# Matrix.net
KiCad netlist of a schematic drawn in Altium Designer
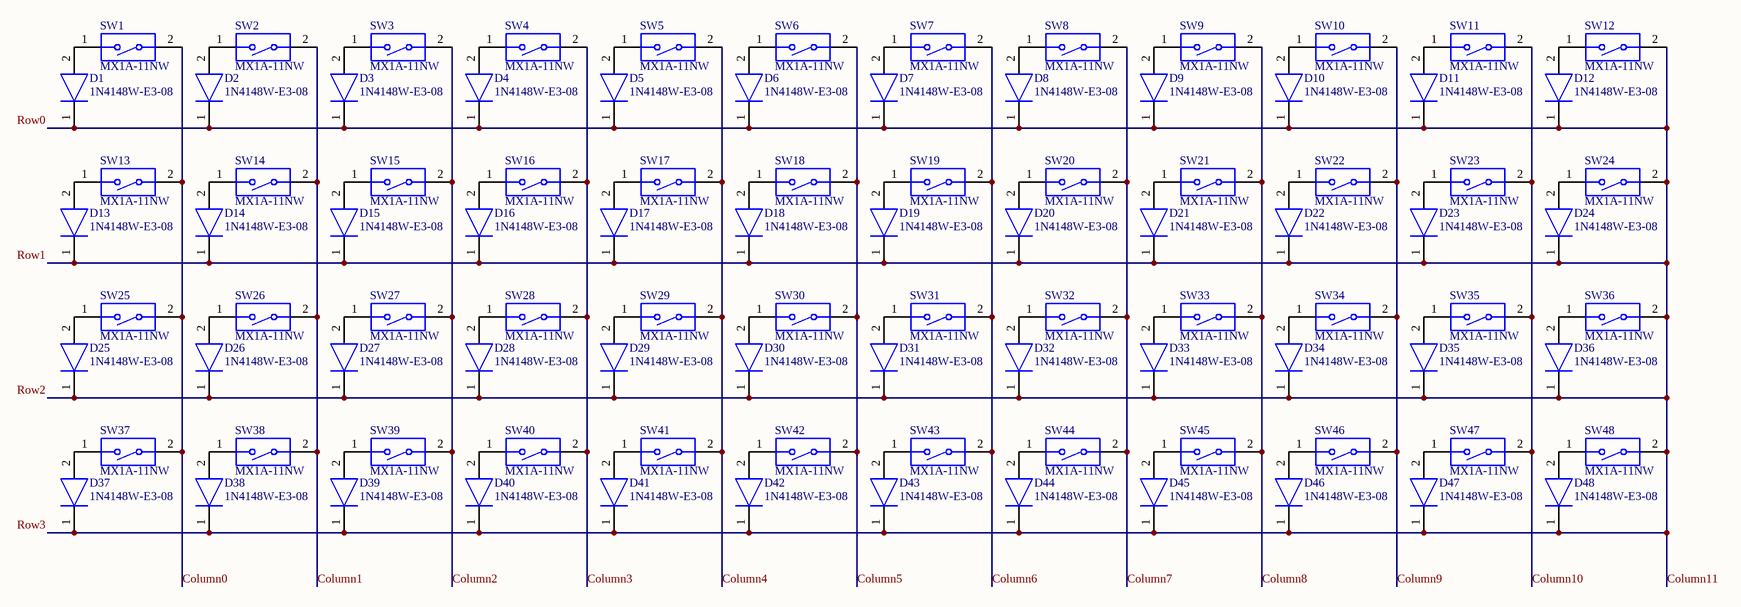
[diagram p0: Matrix.SchDoc]

(export (version "E")
  (design (tool "Eeschema 10.0.6"))
  (components
    (comp (ref "D1")
      (value "1N4148W-E3-08")
      (footprint "SamacSys:SOD3716X135N")
      (description "Diode")
      (fields (field (name "MOUSER PART NUMBER") "78-1N4148W-E3-08"))
      (libsource (lib "*") (part "1N4148W-E3-08"))
    )
    (comp (ref "D2")
      (value "1N4148W-E3-08")
      (footprint "SamacSys:SOD3716X135N")
      (description "Diode")
      (fields (field (name "MOUSER PART NUMBER") "78-1N4148W-E3-08"))
      (libsource (lib "*") (part "1N4148W-E3-08"))
    )
    (comp (ref "D3")
      (value "1N4148W-E3-08")
      (footprint "SamacSys:SOD3716X135N")
      (description "Diode")
      (fields (field (name "MOUSER PART NUMBER") "78-1N4148W-E3-08"))
      (libsource (lib "*") (part "1N4148W-E3-08"))
    )
    (comp (ref "D4")
      (value "1N4148W-E3-08")
      (footprint "SamacSys:SOD3716X135N")
      (description "Diode")
      (fields (field (name "MOUSER PART NUMBER") "78-1N4148W-E3-08"))
      (libsource (lib "*") (part "1N4148W-E3-08"))
    )
    (comp (ref "D5")
      (value "1N4148W-E3-08")
      (footprint "SamacSys:SOD3716X135N")
      (description "Diode")
      (fields (field (name "MOUSER PART NUMBER") "78-1N4148W-E3-08"))
      (libsource (lib "*") (part "1N4148W-E3-08"))
    )
    (comp (ref "D6")
      (value "1N4148W-E3-08")
      (footprint "SamacSys:SOD3716X135N")
      (description "Diode")
      (fields (field (name "MOUSER PART NUMBER") "78-1N4148W-E3-08"))
      (libsource (lib "*") (part "1N4148W-E3-08"))
    )
    (comp (ref "D7")
      (value "1N4148W-E3-08")
      (footprint "SamacSys:SOD3716X135N")
      (description "Diode")
      (fields (field (name "MOUSER PART NUMBER") "78-1N4148W-E3-08"))
      (libsource (lib "*") (part "1N4148W-E3-08"))
    )
    (comp (ref "D8")
      (value "1N4148W-E3-08")
      (footprint "SamacSys:SOD3716X135N")
      (description "Diode")
      (fields (field (name "MOUSER PART NUMBER") "78-1N4148W-E3-08"))
      (libsource (lib "*") (part "1N4148W-E3-08"))
    )
    (comp (ref "D9")
      (value "1N4148W-E3-08")
      (footprint "SamacSys:SOD3716X135N")
      (description "Diode")
      (fields (field (name "MOUSER PART NUMBER") "78-1N4148W-E3-08"))
      (libsource (lib "*") (part "1N4148W-E3-08"))
    )
    (comp (ref "D10")
      (value "1N4148W-E3-08")
      (footprint "SamacSys:SOD3716X135N")
      (description "Diode")
      (fields (field (name "MOUSER PART NUMBER") "78-1N4148W-E3-08"))
      (libsource (lib "*") (part "1N4148W-E3-08"))
    )
    (comp (ref "D11")
      (value "1N4148W-E3-08")
      (footprint "SamacSys:SOD3716X135N")
      (description "Diode")
      (fields (field (name "MOUSER PART NUMBER") "78-1N4148W-E3-08"))
      (libsource (lib "*") (part "1N4148W-E3-08"))
    )
    (comp (ref "D12")
      (value "1N4148W-E3-08")
      (footprint "SamacSys:SOD3716X135N")
      (description "Diode")
      (fields (field (name "MOUSER PART NUMBER") "78-1N4148W-E3-08"))
      (libsource (lib "*") (part "1N4148W-E3-08"))
    )
    (comp (ref "D13")
      (value "1N4148W-E3-08")
      (footprint "SamacSys:SOD3716X135N")
      (description "Diode")
      (fields (field (name "MOUSER PART NUMBER") "78-1N4148W-E3-08"))
      (libsource (lib "*") (part "1N4148W-E3-08"))
    )
    (comp (ref "D14")
      (value "1N4148W-E3-08")
      (footprint "SamacSys:SOD3716X135N")
      (description "Diode")
      (fields (field (name "MOUSER PART NUMBER") "78-1N4148W-E3-08"))
      (libsource (lib "*") (part "1N4148W-E3-08"))
    )
    (comp (ref "D15")
      (value "1N4148W-E3-08")
      (footprint "SamacSys:SOD3716X135N")
      (description "Diode")
      (fields (field (name "MOUSER PART NUMBER") "78-1N4148W-E3-08"))
      (libsource (lib "*") (part "1N4148W-E3-08"))
    )
    (comp (ref "D16")
      (value "1N4148W-E3-08")
      (footprint "SamacSys:SOD3716X135N")
      (description "Diode")
      (fields (field (name "MOUSER PART NUMBER") "78-1N4148W-E3-08"))
      (libsource (lib "*") (part "1N4148W-E3-08"))
    )
    (comp (ref "D17")
      (value "1N4148W-E3-08")
      (footprint "SamacSys:SOD3716X135N")
      (description "Diode")
      (fields (field (name "MOUSER PART NUMBER") "78-1N4148W-E3-08"))
      (libsource (lib "*") (part "1N4148W-E3-08"))
    )
    (comp (ref "D18")
      (value "1N4148W-E3-08")
      (footprint "SamacSys:SOD3716X135N")
      (description "Diode")
      (fields (field (name "MOUSER PART NUMBER") "78-1N4148W-E3-08"))
      (libsource (lib "*") (part "1N4148W-E3-08"))
    )
    (comp (ref "D19")
      (value "1N4148W-E3-08")
      (footprint "SamacSys:SOD3716X135N")
      (description "Diode")
      (fields (field (name "MOUSER PART NUMBER") "78-1N4148W-E3-08"))
      (libsource (lib "*") (part "1N4148W-E3-08"))
    )
    (comp (ref "D20")
      (value "1N4148W-E3-08")
      (footprint "SamacSys:SOD3716X135N")
      (description "Diode")
      (fields (field (name "MOUSER PART NUMBER") "78-1N4148W-E3-08"))
      (libsource (lib "*") (part "1N4148W-E3-08"))
    )
    (comp (ref "D21")
      (value "1N4148W-E3-08")
      (footprint "SamacSys:SOD3716X135N")
      (description "Diode")
      (fields (field (name "MOUSER PART NUMBER") "78-1N4148W-E3-08"))
      (libsource (lib "*") (part "1N4148W-E3-08"))
    )
    (comp (ref "D22")
      (value "1N4148W-E3-08")
      (footprint "SamacSys:SOD3716X135N")
      (description "Diode")
      (fields (field (name "MOUSER PART NUMBER") "78-1N4148W-E3-08"))
      (libsource (lib "*") (part "1N4148W-E3-08"))
    )
    (comp (ref "D23")
      (value "1N4148W-E3-08")
      (footprint "SamacSys:SOD3716X135N")
      (description "Diode")
      (fields (field (name "MOUSER PART NUMBER") "78-1N4148W-E3-08"))
      (libsource (lib "*") (part "1N4148W-E3-08"))
    )
    (comp (ref "D24")
      (value "1N4148W-E3-08")
      (footprint "SamacSys:SOD3716X135N")
      (description "Diode")
      (fields (field (name "MOUSER PART NUMBER") "78-1N4148W-E3-08"))
      (libsource (lib "*") (part "1N4148W-E3-08"))
    )
    (comp (ref "D25")
      (value "1N4148W-E3-08")
      (footprint "SamacSys:SOD3716X135N")
      (description "Diode")
      (fields (field (name "MOUSER PART NUMBER") "78-1N4148W-E3-08"))
      (libsource (lib "*") (part "1N4148W-E3-08"))
    )
    (comp (ref "D26")
      (value "1N4148W-E3-08")
      (footprint "SamacSys:SOD3716X135N")
      (description "Diode")
      (fields (field (name "MOUSER PART NUMBER") "78-1N4148W-E3-08"))
      (libsource (lib "*") (part "1N4148W-E3-08"))
    )
    (comp (ref "D27")
      (value "1N4148W-E3-08")
      (footprint "SamacSys:SOD3716X135N")
      (description "Diode")
      (fields (field (name "MOUSER PART NUMBER") "78-1N4148W-E3-08"))
      (libsource (lib "*") (part "1N4148W-E3-08"))
    )
    (comp (ref "D28")
      (value "1N4148W-E3-08")
      (footprint "SamacSys:SOD3716X135N")
      (description "Diode")
      (fields (field (name "MOUSER PART NUMBER") "78-1N4148W-E3-08"))
      (libsource (lib "*") (part "1N4148W-E3-08"))
    )
    (comp (ref "D29")
      (value "1N4148W-E3-08")
      (footprint "SamacSys:SOD3716X135N")
      (description "Diode")
      (fields (field (name "MOUSER PART NUMBER") "78-1N4148W-E3-08"))
      (libsource (lib "*") (part "1N4148W-E3-08"))
    )
    (comp (ref "D30")
      (value "1N4148W-E3-08")
      (footprint "SamacSys:SOD3716X135N")
      (description "Diode")
      (fields (field (name "MOUSER PART NUMBER") "78-1N4148W-E3-08"))
      (libsource (lib "*") (part "1N4148W-E3-08"))
    )
    (comp (ref "D31")
      (value "1N4148W-E3-08")
      (footprint "SamacSys:SOD3716X135N")
      (description "Diode")
      (fields (field (name "MOUSER PART NUMBER") "78-1N4148W-E3-08"))
      (libsource (lib "*") (part "1N4148W-E3-08"))
    )
    (comp (ref "D32")
      (value "1N4148W-E3-08")
      (footprint "SamacSys:SOD3716X135N")
      (description "Diode")
      (fields (field (name "MOUSER PART NUMBER") "78-1N4148W-E3-08"))
      (libsource (lib "*") (part "1N4148W-E3-08"))
    )
    (comp (ref "D33")
      (value "1N4148W-E3-08")
      (footprint "SamacSys:SOD3716X135N")
      (description "Diode")
      (fields (field (name "MOUSER PART NUMBER") "78-1N4148W-E3-08"))
      (libsource (lib "*") (part "1N4148W-E3-08"))
    )
    (comp (ref "D34")
      (value "1N4148W-E3-08")
      (footprint "SamacSys:SOD3716X135N")
      (description "Diode")
      (fields (field (name "MOUSER PART NUMBER") "78-1N4148W-E3-08"))
      (libsource (lib "*") (part "1N4148W-E3-08"))
    )
    (comp (ref "D35")
      (value "1N4148W-E3-08")
      (footprint "SamacSys:SOD3716X135N")
      (description "Diode")
      (fields (field (name "MOUSER PART NUMBER") "78-1N4148W-E3-08"))
      (libsource (lib "*") (part "1N4148W-E3-08"))
    )
    (comp (ref "D36")
      (value "1N4148W-E3-08")
      (footprint "SamacSys:SOD3716X135N")
      (description "Diode")
      (fields (field (name "MOUSER PART NUMBER") "78-1N4148W-E3-08"))
      (libsource (lib "*") (part "1N4148W-E3-08"))
    )
    (comp (ref "D37")
      (value "1N4148W-E3-08")
      (footprint "SamacSys:SOD3716X135N")
      (description "Diode")
      (fields (field (name "MOUSER PART NUMBER") "78-1N4148W-E3-08"))
      (libsource (lib "*") (part "1N4148W-E3-08"))
    )
    (comp (ref "D38")
      (value "1N4148W-E3-08")
      (footprint "SamacSys:SOD3716X135N")
      (description "Diode")
      (fields (field (name "MOUSER PART NUMBER") "78-1N4148W-E3-08"))
      (libsource (lib "*") (part "1N4148W-E3-08"))
    )
    (comp (ref "D39")
      (value "1N4148W-E3-08")
      (footprint "SamacSys:SOD3716X135N")
      (description "Diode")
      (fields (field (name "MOUSER PART NUMBER") "78-1N4148W-E3-08"))
      (libsource (lib "*") (part "1N4148W-E3-08"))
    )
    (comp (ref "D40")
      (value "1N4148W-E3-08")
      (footprint "SamacSys:SOD3716X135N")
      (description "Diode")
      (fields (field (name "MOUSER PART NUMBER") "78-1N4148W-E3-08"))
      (libsource (lib "*") (part "1N4148W-E3-08"))
    )
    (comp (ref "D41")
      (value "1N4148W-E3-08")
      (footprint "SamacSys:SOD3716X135N")
      (description "Diode")
      (fields (field (name "MOUSER PART NUMBER") "78-1N4148W-E3-08"))
      (libsource (lib "*") (part "1N4148W-E3-08"))
    )
    (comp (ref "D42")
      (value "1N4148W-E3-08")
      (footprint "SamacSys:SOD3716X135N")
      (description "Diode")
      (fields (field (name "MOUSER PART NUMBER") "78-1N4148W-E3-08"))
      (libsource (lib "*") (part "1N4148W-E3-08"))
    )
    (comp (ref "D43")
      (value "1N4148W-E3-08")
      (footprint "SamacSys:SOD3716X135N")
      (description "Diode")
      (fields (field (name "MOUSER PART NUMBER") "78-1N4148W-E3-08"))
      (libsource (lib "*") (part "1N4148W-E3-08"))
    )
    (comp (ref "D44")
      (value "1N4148W-E3-08")
      (footprint "SamacSys:SOD3716X135N")
      (description "Diode")
      (fields (field (name "MOUSER PART NUMBER") "78-1N4148W-E3-08"))
      (libsource (lib "*") (part "1N4148W-E3-08"))
    )
    (comp (ref "D45")
      (value "1N4148W-E3-08")
      (footprint "SamacSys:SOD3716X135N")
      (description "Diode")
      (fields (field (name "MOUSER PART NUMBER") "78-1N4148W-E3-08"))
      (libsource (lib "*") (part "1N4148W-E3-08"))
    )
    (comp (ref "D46")
      (value "1N4148W-E3-08")
      (footprint "SamacSys:SOD3716X135N")
      (description "Diode")
      (fields (field (name "MOUSER PART NUMBER") "78-1N4148W-E3-08"))
      (libsource (lib "*") (part "1N4148W-E3-08"))
    )
    (comp (ref "D47")
      (value "1N4148W-E3-08")
      (footprint "SamacSys:SOD3716X135N")
      (description "Diode")
      (fields (field (name "MOUSER PART NUMBER") "78-1N4148W-E3-08"))
      (libsource (lib "*") (part "1N4148W-E3-08"))
    )
    (comp (ref "D48")
      (value "1N4148W-E3-08")
      (footprint "SamacSys:SOD3716X135N")
      (description "Diode")
      (fields (field (name "MOUSER PART NUMBER") "78-1N4148W-E3-08"))
      (libsource (lib "*") (part "1N4148W-E3-08"))
    )
    (comp (ref "SW1")
      (value "MX1A-11NW")
      (footprint "CHRY-MX1A-11NW_V")
      (description "Keylock Switch, 12 V, -10 to 70 degC, 2-Pin THD, RoHS, Bulk")
      (fields (field (name "MANUFACTURER") "Cherry") (field (name "PART NO") "MX1A11NW"))
      (libsource (lib "mx1a-11nw") (part "CMP-2000-06786-1"))
    )
    (comp (ref "SW2")
      (value "MX1A-11NW")
      (footprint "CHRY-MX1A-11NW_V")
      (description "Keylock Switch, 12 V, -10 to 70 degC, 2-Pin THD, RoHS, Bulk")
      (fields (field (name "MANUFACTURER") "Cherry") (field (name "PART NO") "MX1A11NW"))
      (libsource (lib "mx1a-11nw") (part "CMP-2000-06786-1"))
    )
    (comp (ref "SW3")
      (value "MX1A-11NW")
      (footprint "CHRY-MX1A-11NW_V")
      (description "Keylock Switch, 12 V, -10 to 70 degC, 2-Pin THD, RoHS, Bulk")
      (fields (field (name "MANUFACTURER") "Cherry") (field (name "PART NO") "MX1A11NW"))
      (libsource (lib "mx1a-11nw") (part "CMP-2000-06786-1"))
    )
    (comp (ref "SW4")
      (value "MX1A-11NW")
      (footprint "CHRY-MX1A-11NW_V")
      (description "Keylock Switch, 12 V, -10 to 70 degC, 2-Pin THD, RoHS, Bulk")
      (fields (field (name "MANUFACTURER") "Cherry") (field (name "PART NO") "MX1A11NW"))
      (libsource (lib "mx1a-11nw") (part "CMP-2000-06786-1"))
    )
    (comp (ref "SW5")
      (value "MX1A-11NW")
      (footprint "CHRY-MX1A-11NW_V")
      (description "Keylock Switch, 12 V, -10 to 70 degC, 2-Pin THD, RoHS, Bulk")
      (fields (field (name "MANUFACTURER") "Cherry") (field (name "PART NO") "MX1A11NW"))
      (libsource (lib "mx1a-11nw") (part "CMP-2000-06786-1"))
    )
    (comp (ref "SW6")
      (value "MX1A-11NW")
      (footprint "CHRY-MX1A-11NW_V")
      (description "Keylock Switch, 12 V, -10 to 70 degC, 2-Pin THD, RoHS, Bulk")
      (fields (field (name "MANUFACTURER") "Cherry") (field (name "PART NO") "MX1A11NW"))
      (libsource (lib "mx1a-11nw") (part "CMP-2000-06786-1"))
    )
    (comp (ref "SW7")
      (value "MX1A-11NW")
      (footprint "CHRY-MX1A-11NW_V")
      (description "Keylock Switch, 12 V, -10 to 70 degC, 2-Pin THD, RoHS, Bulk")
      (fields (field (name "MANUFACTURER") "Cherry") (field (name "PART NO") "MX1A11NW"))
      (libsource (lib "mx1a-11nw") (part "CMP-2000-06786-1"))
    )
    (comp (ref "SW8")
      (value "MX1A-11NW")
      (footprint "CHRY-MX1A-11NW_V")
      (description "Keylock Switch, 12 V, -10 to 70 degC, 2-Pin THD, RoHS, Bulk")
      (fields (field (name "MANUFACTURER") "Cherry") (field (name "PART NO") "MX1A11NW"))
      (libsource (lib "mx1a-11nw") (part "CMP-2000-06786-1"))
    )
    (comp (ref "SW9")
      (value "MX1A-11NW")
      (footprint "CHRY-MX1A-11NW_V")
      (description "Keylock Switch, 12 V, -10 to 70 degC, 2-Pin THD, RoHS, Bulk")
      (fields (field (name "MANUFACTURER") "Cherry") (field (name "PART NO") "MX1A11NW"))
      (libsource (lib "mx1a-11nw") (part "CMP-2000-06786-1"))
    )
    (comp (ref "SW10")
      (value "MX1A-11NW")
      (footprint "CHRY-MX1A-11NW_V")
      (description "Keylock Switch, 12 V, -10 to 70 degC, 2-Pin THD, RoHS, Bulk")
      (fields (field (name "MANUFACTURER") "Cherry") (field (name "PART NO") "MX1A11NW"))
      (libsource (lib "mx1a-11nw") (part "CMP-2000-06786-1"))
    )
    (comp (ref "SW11")
      (value "MX1A-11NW")
      (footprint "CHRY-MX1A-11NW_V")
      (description "Keylock Switch, 12 V, -10 to 70 degC, 2-Pin THD, RoHS, Bulk")
      (fields (field (name "MANUFACTURER") "Cherry") (field (name "PART NO") "MX1A11NW"))
      (libsource (lib "mx1a-11nw") (part "CMP-2000-06786-1"))
    )
    (comp (ref "SW12")
      (value "MX1A-11NW")
      (footprint "CHRY-MX1A-11NW_V")
      (description "Keylock Switch, 12 V, -10 to 70 degC, 2-Pin THD, RoHS, Bulk")
      (fields (field (name "MANUFACTURER") "Cherry") (field (name "PART NO") "MX1A11NW"))
      (libsource (lib "mx1a-11nw") (part "CMP-2000-06786-1"))
    )
    (comp (ref "SW13")
      (value "MX1A-11NW")
      (footprint "CHRY-MX1A-11NW_V")
      (description "Keylock Switch, 12 V, -10 to 70 degC, 2-Pin THD, RoHS, Bulk")
      (fields (field (name "MANUFACTURER") "Cherry") (field (name "PART NO") "MX1A11NW"))
      (libsource (lib "mx1a-11nw") (part "CMP-2000-06786-1"))
    )
    (comp (ref "SW14")
      (value "MX1A-11NW")
      (footprint "CHRY-MX1A-11NW_V")
      (description "Keylock Switch, 12 V, -10 to 70 degC, 2-Pin THD, RoHS, Bulk")
      (fields (field (name "MANUFACTURER") "Cherry") (field (name "PART NO") "MX1A11NW"))
      (libsource (lib "mx1a-11nw") (part "CMP-2000-06786-1"))
    )
    (comp (ref "SW15")
      (value "MX1A-11NW")
      (footprint "CHRY-MX1A-11NW_V")
      (description "Keylock Switch, 12 V, -10 to 70 degC, 2-Pin THD, RoHS, Bulk")
      (fields (field (name "MANUFACTURER") "Cherry") (field (name "PART NO") "MX1A11NW"))
      (libsource (lib "mx1a-11nw") (part "CMP-2000-06786-1"))
    )
    (comp (ref "SW16")
      (value "MX1A-11NW")
      (footprint "CHRY-MX1A-11NW_V")
      (description "Keylock Switch, 12 V, -10 to 70 degC, 2-Pin THD, RoHS, Bulk")
      (fields (field (name "MANUFACTURER") "Cherry") (field (name "PART NO") "MX1A11NW"))
      (libsource (lib "mx1a-11nw") (part "CMP-2000-06786-1"))
    )
    (comp (ref "SW17")
      (value "MX1A-11NW")
      (footprint "CHRY-MX1A-11NW_V")
      (description "Keylock Switch, 12 V, -10 to 70 degC, 2-Pin THD, RoHS, Bulk")
      (fields (field (name "MANUFACTURER") "Cherry") (field (name "PART NO") "MX1A11NW"))
      (libsource (lib "mx1a-11nw") (part "CMP-2000-06786-1"))
    )
    (comp (ref "SW18")
      (value "MX1A-11NW")
      (footprint "CHRY-MX1A-11NW_V")
      (description "Keylock Switch, 12 V, -10 to 70 degC, 2-Pin THD, RoHS, Bulk")
      (fields (field (name "MANUFACTURER") "Cherry") (field (name "PART NO") "MX1A11NW"))
      (libsource (lib "mx1a-11nw") (part "CMP-2000-06786-1"))
    )
    (comp (ref "SW19")
      (value "MX1A-11NW")
      (footprint "CHRY-MX1A-11NW_V")
      (description "Keylock Switch, 12 V, -10 to 70 degC, 2-Pin THD, RoHS, Bulk")
      (fields (field (name "MANUFACTURER") "Cherry") (field (name "PART NO") "MX1A11NW"))
      (libsource (lib "mx1a-11nw") (part "CMP-2000-06786-1"))
    )
    (comp (ref "SW20")
      (value "MX1A-11NW")
      (footprint "CHRY-MX1A-11NW_V")
      (description "Keylock Switch, 12 V, -10 to 70 degC, 2-Pin THD, RoHS, Bulk")
      (fields (field (name "MANUFACTURER") "Cherry") (field (name "PART NO") "MX1A11NW"))
      (libsource (lib "mx1a-11nw") (part "CMP-2000-06786-1"))
    )
    (comp (ref "SW21")
      (value "MX1A-11NW")
      (footprint "CHRY-MX1A-11NW_V")
      (description "Keylock Switch, 12 V, -10 to 70 degC, 2-Pin THD, RoHS, Bulk")
      (fields (field (name "MANUFACTURER") "Cherry") (field (name "PART NO") "MX1A11NW"))
      (libsource (lib "mx1a-11nw") (part "CMP-2000-06786-1"))
    )
    (comp (ref "SW22")
      (value "MX1A-11NW")
      (footprint "CHRY-MX1A-11NW_V")
      (description "Keylock Switch, 12 V, -10 to 70 degC, 2-Pin THD, RoHS, Bulk")
      (fields (field (name "MANUFACTURER") "Cherry") (field (name "PART NO") "MX1A11NW"))
      (libsource (lib "mx1a-11nw") (part "CMP-2000-06786-1"))
    )
    (comp (ref "SW23")
      (value "MX1A-11NW")
      (footprint "CHRY-MX1A-11NW_V")
      (description "Keylock Switch, 12 V, -10 to 70 degC, 2-Pin THD, RoHS, Bulk")
      (fields (field (name "MANUFACTURER") "Cherry") (field (name "PART NO") "MX1A11NW"))
      (libsource (lib "mx1a-11nw") (part "CMP-2000-06786-1"))
    )
    (comp (ref "SW24")
      (value "MX1A-11NW")
      (footprint "CHRY-MX1A-11NW_V")
      (description "Keylock Switch, 12 V, -10 to 70 degC, 2-Pin THD, RoHS, Bulk")
      (fields (field (name "MANUFACTURER") "Cherry") (field (name "PART NO") "MX1A11NW"))
      (libsource (lib "mx1a-11nw") (part "CMP-2000-06786-1"))
    )
    (comp (ref "SW25")
      (value "MX1A-11NW")
      (footprint "CHRY-MX1A-11NW_V")
      (description "Keylock Switch, 12 V, -10 to 70 degC, 2-Pin THD, RoHS, Bulk")
      (fields (field (name "MANUFACTURER") "Cherry") (field (name "PART NO") "MX1A11NW"))
      (libsource (lib "mx1a-11nw") (part "CMP-2000-06786-1"))
    )
    (comp (ref "SW26")
      (value "MX1A-11NW")
      (footprint "CHRY-MX1A-11NW_V")
      (description "Keylock Switch, 12 V, -10 to 70 degC, 2-Pin THD, RoHS, Bulk")
      (fields (field (name "MANUFACTURER") "Cherry") (field (name "PART NO") "MX1A11NW"))
      (libsource (lib "mx1a-11nw") (part "CMP-2000-06786-1"))
    )
    (comp (ref "SW27")
      (value "MX1A-11NW")
      (footprint "CHRY-MX1A-11NW_V")
      (description "Keylock Switch, 12 V, -10 to 70 degC, 2-Pin THD, RoHS, Bulk")
      (fields (field (name "MANUFACTURER") "Cherry") (field (name "PART NO") "MX1A11NW"))
      (libsource (lib "mx1a-11nw") (part "CMP-2000-06786-1"))
    )
    (comp (ref "SW28")
      (value "MX1A-11NW")
      (footprint "CHRY-MX1A-11NW_V")
      (description "Keylock Switch, 12 V, -10 to 70 degC, 2-Pin THD, RoHS, Bulk")
      (fields (field (name "MANUFACTURER") "Cherry") (field (name "PART NO") "MX1A11NW"))
      (libsource (lib "mx1a-11nw") (part "CMP-2000-06786-1"))
    )
    (comp (ref "SW29")
      (value "MX1A-11NW")
      (footprint "CHRY-MX1A-11NW_V")
      (description "Keylock Switch, 12 V, -10 to 70 degC, 2-Pin THD, RoHS, Bulk")
      (fields (field (name "MANUFACTURER") "Cherry") (field (name "PART NO") "MX1A11NW"))
      (libsource (lib "mx1a-11nw") (part "CMP-2000-06786-1"))
    )
    (comp (ref "SW30")
      (value "MX1A-11NW")
      (footprint "CHRY-MX1A-11NW_V")
      (description "Keylock Switch, 12 V, -10 to 70 degC, 2-Pin THD, RoHS, Bulk")
      (fields (field (name "MANUFACTURER") "Cherry") (field (name "PART NO") "MX1A11NW"))
      (libsource (lib "mx1a-11nw") (part "CMP-2000-06786-1"))
    )
    (comp (ref "SW31")
      (value "MX1A-11NW")
      (footprint "CHRY-MX1A-11NW_V")
      (description "Keylock Switch, 12 V, -10 to 70 degC, 2-Pin THD, RoHS, Bulk")
      (fields (field (name "MANUFACTURER") "Cherry") (field (name "PART NO") "MX1A11NW"))
      (libsource (lib "mx1a-11nw") (part "CMP-2000-06786-1"))
    )
    (comp (ref "SW32")
      (value "MX1A-11NW")
      (footprint "CHRY-MX1A-11NW_V")
      (description "Keylock Switch, 12 V, -10 to 70 degC, 2-Pin THD, RoHS, Bulk")
      (fields (field (name "MANUFACTURER") "Cherry") (field (name "PART NO") "MX1A11NW"))
      (libsource (lib "mx1a-11nw") (part "CMP-2000-06786-1"))
    )
    (comp (ref "SW33")
      (value "MX1A-11NW")
      (footprint "CHRY-MX1A-11NW_V")
      (description "Keylock Switch, 12 V, -10 to 70 degC, 2-Pin THD, RoHS, Bulk")
      (fields (field (name "MANUFACTURER") "Cherry") (field (name "PART NO") "MX1A11NW"))
      (libsource (lib "mx1a-11nw") (part "CMP-2000-06786-1"))
    )
    (comp (ref "SW34")
      (value "MX1A-11NW")
      (footprint "CHRY-MX1A-11NW_V")
      (description "Keylock Switch, 12 V, -10 to 70 degC, 2-Pin THD, RoHS, Bulk")
      (fields (field (name "MANUFACTURER") "Cherry") (field (name "PART NO") "MX1A11NW"))
      (libsource (lib "mx1a-11nw") (part "CMP-2000-06786-1"))
    )
    (comp (ref "SW35")
      (value "MX1A-11NW")
      (footprint "CHRY-MX1A-11NW_V")
      (description "Keylock Switch, 12 V, -10 to 70 degC, 2-Pin THD, RoHS, Bulk")
      (fields (field (name "MANUFACTURER") "Cherry") (field (name "PART NO") "MX1A11NW"))
      (libsource (lib "mx1a-11nw") (part "CMP-2000-06786-1"))
    )
    (comp (ref "SW36")
      (value "MX1A-11NW")
      (footprint "CHRY-MX1A-11NW_V")
      (description "Keylock Switch, 12 V, -10 to 70 degC, 2-Pin THD, RoHS, Bulk")
      (fields (field (name "MANUFACTURER") "Cherry") (field (name "PART NO") "MX1A11NW"))
      (libsource (lib "mx1a-11nw") (part "CMP-2000-06786-1"))
    )
    (comp (ref "SW37")
      (value "MX1A-11NW")
      (footprint "CHRY-MX1A-11NW_V")
      (description "Keylock Switch, 12 V, -10 to 70 degC, 2-Pin THD, RoHS, Bulk")
      (fields (field (name "MANUFACTURER") "Cherry") (field (name "PART NO") "MX1A11NW"))
      (libsource (lib "mx1a-11nw") (part "CMP-2000-06786-1"))
    )
    (comp (ref "SW38")
      (value "MX1A-11NW")
      (footprint "CHRY-MX1A-11NW_V")
      (description "Keylock Switch, 12 V, -10 to 70 degC, 2-Pin THD, RoHS, Bulk")
      (fields (field (name "MANUFACTURER") "Cherry") (field (name "PART NO") "MX1A11NW"))
      (libsource (lib "mx1a-11nw") (part "CMP-2000-06786-1"))
    )
    (comp (ref "SW39")
      (value "MX1A-11NW")
      (footprint "CHRY-MX1A-11NW_V")
      (description "Keylock Switch, 12 V, -10 to 70 degC, 2-Pin THD, RoHS, Bulk")
      (fields (field (name "MANUFACTURER") "Cherry") (field (name "PART NO") "MX1A11NW"))
      (libsource (lib "mx1a-11nw") (part "CMP-2000-06786-1"))
    )
    (comp (ref "SW40")
      (value "MX1A-11NW")
      (footprint "CHRY-MX1A-11NW_V")
      (description "Keylock Switch, 12 V, -10 to 70 degC, 2-Pin THD, RoHS, Bulk")
      (fields (field (name "MANUFACTURER") "Cherry") (field (name "PART NO") "MX1A11NW"))
      (libsource (lib "mx1a-11nw") (part "CMP-2000-06786-1"))
    )
    (comp (ref "SW41")
      (value "MX1A-11NW")
      (footprint "CHRY-MX1A-11NW_V")
      (description "Keylock Switch, 12 V, -10 to 70 degC, 2-Pin THD, RoHS, Bulk")
      (fields (field (name "MANUFACTURER") "Cherry") (field (name "PART NO") "MX1A11NW"))
      (libsource (lib "mx1a-11nw") (part "CMP-2000-06786-1"))
    )
    (comp (ref "SW42")
      (value "MX1A-11NW")
      (footprint "CHRY-MX1A-11NW_V")
      (description "Keylock Switch, 12 V, -10 to 70 degC, 2-Pin THD, RoHS, Bulk")
      (fields (field (name "MANUFACTURER") "Cherry") (field (name "PART NO") "MX1A11NW"))
      (libsource (lib "mx1a-11nw") (part "CMP-2000-06786-1"))
    )
    (comp (ref "SW43")
      (value "MX1A-11NW")
      (footprint "CHRY-MX1A-11NW_V")
      (description "Keylock Switch, 12 V, -10 to 70 degC, 2-Pin THD, RoHS, Bulk")
      (fields (field (name "MANUFACTURER") "Cherry") (field (name "PART NO") "MX1A11NW"))
      (libsource (lib "mx1a-11nw") (part "CMP-2000-06786-1"))
    )
    (comp (ref "SW44")
      (value "MX1A-11NW")
      (footprint "CHRY-MX1A-11NW_V")
      (description "Keylock Switch, 12 V, -10 to 70 degC, 2-Pin THD, RoHS, Bulk")
      (fields (field (name "MANUFACTURER") "Cherry") (field (name "PART NO") "MX1A11NW"))
      (libsource (lib "mx1a-11nw") (part "CMP-2000-06786-1"))
    )
    (comp (ref "SW45")
      (value "MX1A-11NW")
      (footprint "CHRY-MX1A-11NW_V")
      (description "Keylock Switch, 12 V, -10 to 70 degC, 2-Pin THD, RoHS, Bulk")
      (fields (field (name "MANUFACTURER") "Cherry") (field (name "PART NO") "MX1A11NW"))
      (libsource (lib "mx1a-11nw") (part "CMP-2000-06786-1"))
    )
    (comp (ref "SW46")
      (value "MX1A-11NW")
      (footprint "CHRY-MX1A-11NW_V")
      (description "Keylock Switch, 12 V, -10 to 70 degC, 2-Pin THD, RoHS, Bulk")
      (fields (field (name "MANUFACTURER") "Cherry") (field (name "PART NO") "MX1A11NW"))
      (libsource (lib "mx1a-11nw") (part "CMP-2000-06786-1"))
    )
    (comp (ref "SW47")
      (value "MX1A-11NW")
      (footprint "CHRY-MX1A-11NW_V")
      (description "Keylock Switch, 12 V, -10 to 70 degC, 2-Pin THD, RoHS, Bulk")
      (fields (field (name "MANUFACTURER") "Cherry") (field (name "PART NO") "MX1A11NW"))
      (libsource (lib "mx1a-11nw") (part "CMP-2000-06786-1"))
    )
    (comp (ref "SW48")
      (value "MX1A-11NW")
      (footprint "CHRY-MX1A-11NW_V")
      (description "Keylock Switch, 12 V, -10 to 70 degC, 2-Pin THD, RoHS, Bulk")
      (fields (field (name "MANUFACTURER") "Cherry") (field (name "PART NO") "MX1A11NW"))
      (libsource (lib "mx1a-11nw") (part "CMP-2000-06786-1"))
    )
  )
  (nets
    (net (code "1") (name "/Column0") (class "Default")
      (node (ref "SW1") (pin "2") (pinfunction "2_2") (pintype "passive"))
      (node (ref "SW13") (pin "2") (pinfunction "2_2") (pintype "passive"))
      (node (ref "SW25") (pin "2") (pinfunction "2_2") (pintype "passive"))
      (node (ref "SW37") (pin "2") (pinfunction "2_2") (pintype "passive"))
    )
    (net (code "2") (name "/Column1") (class "Default")
      (node (ref "SW14") (pin "2") (pinfunction "2_2") (pintype "passive"))
      (node (ref "SW2") (pin "2") (pinfunction "2_2") (pintype "passive"))
      (node (ref "SW26") (pin "2") (pinfunction "2_2") (pintype "passive"))
      (node (ref "SW38") (pin "2") (pinfunction "2_2") (pintype "passive"))
    )
    (net (code "3") (name "/Column2") (class "Default")
      (node (ref "SW15") (pin "2") (pinfunction "2_2") (pintype "passive"))
      (node (ref "SW27") (pin "2") (pinfunction "2_2") (pintype "passive"))
      (node (ref "SW3") (pin "2") (pinfunction "2_2") (pintype "passive"))
      (node (ref "SW39") (pin "2") (pinfunction "2_2") (pintype "passive"))
    )
    (net (code "4") (name "/Column3") (class "Default")
      (node (ref "SW16") (pin "2") (pinfunction "2_2") (pintype "passive"))
      (node (ref "SW28") (pin "2") (pinfunction "2_2") (pintype "passive"))
      (node (ref "SW4") (pin "2") (pinfunction "2_2") (pintype "passive"))
      (node (ref "SW40") (pin "2") (pinfunction "2_2") (pintype "passive"))
    )
    (net (code "5") (name "/Column4") (class "Default")
      (node (ref "SW17") (pin "2") (pinfunction "2_2") (pintype "passive"))
      (node (ref "SW29") (pin "2") (pinfunction "2_2") (pintype "passive"))
      (node (ref "SW41") (pin "2") (pinfunction "2_2") (pintype "passive"))
      (node (ref "SW5") (pin "2") (pinfunction "2_2") (pintype "passive"))
    )
    (net (code "6") (name "/Column5") (class "Default")
      (node (ref "SW18") (pin "2") (pinfunction "2_2") (pintype "passive"))
      (node (ref "SW30") (pin "2") (pinfunction "2_2") (pintype "passive"))
      (node (ref "SW42") (pin "2") (pinfunction "2_2") (pintype "passive"))
      (node (ref "SW6") (pin "2") (pinfunction "2_2") (pintype "passive"))
    )
    (net (code "7") (name "/Column6") (class "Default")
      (node (ref "SW19") (pin "2") (pinfunction "2_2") (pintype "passive"))
      (node (ref "SW31") (pin "2") (pinfunction "2_2") (pintype "passive"))
      (node (ref "SW43") (pin "2") (pinfunction "2_2") (pintype "passive"))
      (node (ref "SW7") (pin "2") (pinfunction "2_2") (pintype "passive"))
    )
    (net (code "8") (name "/Column7") (class "Default")
      (node (ref "SW20") (pin "2") (pinfunction "2_2") (pintype "passive"))
      (node (ref "SW32") (pin "2") (pinfunction "2_2") (pintype "passive"))
      (node (ref "SW44") (pin "2") (pinfunction "2_2") (pintype "passive"))
      (node (ref "SW8") (pin "2") (pinfunction "2_2") (pintype "passive"))
    )
    (net (code "9") (name "/Column8") (class "Default")
      (node (ref "SW21") (pin "2") (pinfunction "2_2") (pintype "passive"))
      (node (ref "SW33") (pin "2") (pinfunction "2_2") (pintype "passive"))
      (node (ref "SW45") (pin "2") (pinfunction "2_2") (pintype "passive"))
      (node (ref "SW9") (pin "2") (pinfunction "2_2") (pintype "passive"))
    )
    (net (code "10") (name "/Column9") (class "Default")
      (node (ref "SW10") (pin "2") (pinfunction "2_2") (pintype "passive"))
      (node (ref "SW22") (pin "2") (pinfunction "2_2") (pintype "passive"))
      (node (ref "SW34") (pin "2") (pinfunction "2_2") (pintype "passive"))
      (node (ref "SW46") (pin "2") (pinfunction "2_2") (pintype "passive"))
    )
    (net (code "11") (name "/Column10") (class "Default")
      (node (ref "SW11") (pin "2") (pinfunction "2_2") (pintype "passive"))
      (node (ref "SW23") (pin "2") (pinfunction "2_2") (pintype "passive"))
      (node (ref "SW35") (pin "2") (pinfunction "2_2") (pintype "passive"))
      (node (ref "SW47") (pin "2") (pinfunction "2_2") (pintype "passive"))
    )
    (net (code "12") (name "/Column11") (class "Default")
      (node (ref "D1") (pin "1") (pinfunction "K_1") (pintype "passive"))
      (node (ref "D10") (pin "1") (pinfunction "K_1") (pintype "passive"))
      (node (ref "D11") (pin "1") (pinfunction "K_1") (pintype "passive"))
      (node (ref "D12") (pin "1") (pinfunction "K_1") (pintype "passive"))
      (node (ref "D13") (pin "1") (pinfunction "K_1") (pintype "passive"))
      (node (ref "D14") (pin "1") (pinfunction "K_1") (pintype "passive"))
      (node (ref "D15") (pin "1") (pinfunction "K_1") (pintype "passive"))
      (node (ref "D16") (pin "1") (pinfunction "K_1") (pintype "passive"))
      (node (ref "D17") (pin "1") (pinfunction "K_1") (pintype "passive"))
      (node (ref "D18") (pin "1") (pinfunction "K_1") (pintype "passive"))
      (node (ref "D19") (pin "1") (pinfunction "K_1") (pintype "passive"))
      (node (ref "D2") (pin "1") (pinfunction "K_1") (pintype "passive"))
      (node (ref "D20") (pin "1") (pinfunction "K_1") (pintype "passive"))
      (node (ref "D21") (pin "1") (pinfunction "K_1") (pintype "passive"))
      (node (ref "D22") (pin "1") (pinfunction "K_1") (pintype "passive"))
      (node (ref "D23") (pin "1") (pinfunction "K_1") (pintype "passive"))
      (node (ref "D24") (pin "1") (pinfunction "K_1") (pintype "passive"))
      (node (ref "D25") (pin "1") (pinfunction "K_1") (pintype "passive"))
      (node (ref "D26") (pin "1") (pinfunction "K_1") (pintype "passive"))
      (node (ref "D27") (pin "1") (pinfunction "K_1") (pintype "passive"))
      (node (ref "D28") (pin "1") (pinfunction "K_1") (pintype "passive"))
      (node (ref "D29") (pin "1") (pinfunction "K_1") (pintype "passive"))
      (node (ref "D3") (pin "1") (pinfunction "K_1") (pintype "passive"))
      (node (ref "D30") (pin "1") (pinfunction "K_1") (pintype "passive"))
      (node (ref "D31") (pin "1") (pinfunction "K_1") (pintype "passive"))
      (node (ref "D32") (pin "1") (pinfunction "K_1") (pintype "passive"))
      (node (ref "D33") (pin "1") (pinfunction "K_1") (pintype "passive"))
      (node (ref "D34") (pin "1") (pinfunction "K_1") (pintype "passive"))
      (node (ref "D35") (pin "1") (pinfunction "K_1") (pintype "passive"))
      (node (ref "D36") (pin "1") (pinfunction "K_1") (pintype "passive"))
      (node (ref "D37") (pin "1") (pinfunction "K_1") (pintype "passive"))
      (node (ref "D38") (pin "1") (pinfunction "K_1") (pintype "passive"))
      (node (ref "D39") (pin "1") (pinfunction "K_1") (pintype "passive"))
      (node (ref "D4") (pin "1") (pinfunction "K_1") (pintype "passive"))
      (node (ref "D40") (pin "1") (pinfunction "K_1") (pintype "passive"))
      (node (ref "D41") (pin "1") (pinfunction "K_1") (pintype "passive"))
      (node (ref "D42") (pin "1") (pinfunction "K_1") (pintype "passive"))
      (node (ref "D43") (pin "1") (pinfunction "K_1") (pintype "passive"))
      (node (ref "D44") (pin "1") (pinfunction "K_1") (pintype "passive"))
      (node (ref "D45") (pin "1") (pinfunction "K_1") (pintype "passive"))
      (node (ref "D46") (pin "1") (pinfunction "K_1") (pintype "passive"))
      (node (ref "D47") (pin "1") (pinfunction "K_1") (pintype "passive"))
      (node (ref "D48") (pin "1") (pinfunction "K_1") (pintype "passive"))
      (node (ref "D5") (pin "1") (pinfunction "K_1") (pintype "passive"))
      (node (ref "D6") (pin "1") (pinfunction "K_1") (pintype "passive"))
      (node (ref "D7") (pin "1") (pinfunction "K_1") (pintype "passive"))
      (node (ref "D8") (pin "1") (pinfunction "K_1") (pintype "passive"))
      (node (ref "D9") (pin "1") (pinfunction "K_1") (pintype "passive"))
      (node (ref "SW12") (pin "2") (pinfunction "2_2") (pintype "passive"))
      (node (ref "SW24") (pin "2") (pinfunction "2_2") (pintype "passive"))
      (node (ref "SW36") (pin "2") (pinfunction "2_2") (pintype "passive"))
      (node (ref "SW48") (pin "2") (pinfunction "2_2") (pintype "passive"))
    )
    (net (code "13") (name "Net-(D1-A)") (class "Default")
      (node (ref "D1") (pin "2") (pinfunction "A_2") (pintype "passive"))
      (node (ref "SW1") (pin "1") (pinfunction "1_1") (pintype "passive"))
    )
    (net (code "14") (name "Net-(D2-A)") (class "Default")
      (node (ref "D2") (pin "2") (pinfunction "A_2") (pintype "passive"))
      (node (ref "SW2") (pin "1") (pinfunction "1_1") (pintype "passive"))
    )
    (net (code "15") (name "Net-(D3-A)") (class "Default")
      (node (ref "D3") (pin "2") (pinfunction "A_2") (pintype "passive"))
      (node (ref "SW3") (pin "1") (pinfunction "1_1") (pintype "passive"))
    )
    (net (code "16") (name "Net-(D4-A)") (class "Default")
      (node (ref "D4") (pin "2") (pinfunction "A_2") (pintype "passive"))
      (node (ref "SW4") (pin "1") (pinfunction "1_1") (pintype "passive"))
    )
    (net (code "17") (name "Net-(D5-A)") (class "Default")
      (node (ref "D5") (pin "2") (pinfunction "A_2") (pintype "passive"))
      (node (ref "SW5") (pin "1") (pinfunction "1_1") (pintype "passive"))
    )
    (net (code "18") (name "Net-(D6-A)") (class "Default")
      (node (ref "D6") (pin "2") (pinfunction "A_2") (pintype "passive"))
      (node (ref "SW6") (pin "1") (pinfunction "1_1") (pintype "passive"))
    )
    (net (code "19") (name "Net-(D7-A)") (class "Default")
      (node (ref "D7") (pin "2") (pinfunction "A_2") (pintype "passive"))
      (node (ref "SW7") (pin "1") (pinfunction "1_1") (pintype "passive"))
    )
    (net (code "20") (name "Net-(D8-A)") (class "Default")
      (node (ref "D8") (pin "2") (pinfunction "A_2") (pintype "passive"))
      (node (ref "SW8") (pin "1") (pinfunction "1_1") (pintype "passive"))
    )
    (net (code "21") (name "Net-(D9-A)") (class "Default")
      (node (ref "D9") (pin "2") (pinfunction "A_2") (pintype "passive"))
      (node (ref "SW9") (pin "1") (pinfunction "1_1") (pintype "passive"))
    )
    (net (code "22") (name "Net-(D10-A)") (class "Default")
      (node (ref "D10") (pin "2") (pinfunction "A_2") (pintype "passive"))
      (node (ref "SW10") (pin "1") (pinfunction "1_1") (pintype "passive"))
    )
    (net (code "23") (name "Net-(D11-A)") (class "Default")
      (node (ref "D11") (pin "2") (pinfunction "A_2") (pintype "passive"))
      (node (ref "SW11") (pin "1") (pinfunction "1_1") (pintype "passive"))
    )
    (net (code "24") (name "Net-(D12-A)") (class "Default")
      (node (ref "D12") (pin "2") (pinfunction "A_2") (pintype "passive"))
      (node (ref "SW12") (pin "1") (pinfunction "1_1") (pintype "passive"))
    )
    (net (code "25") (name "Net-(D13-A)") (class "Default")
      (node (ref "D13") (pin "2") (pinfunction "A_2") (pintype "passive"))
      (node (ref "SW13") (pin "1") (pinfunction "1_1") (pintype "passive"))
    )
    (net (code "26") (name "Net-(D14-A)") (class "Default")
      (node (ref "D14") (pin "2") (pinfunction "A_2") (pintype "passive"))
      (node (ref "SW14") (pin "1") (pinfunction "1_1") (pintype "passive"))
    )
    (net (code "27") (name "Net-(D15-A)") (class "Default")
      (node (ref "D15") (pin "2") (pinfunction "A_2") (pintype "passive"))
      (node (ref "SW15") (pin "1") (pinfunction "1_1") (pintype "passive"))
    )
    (net (code "28") (name "Net-(D16-A)") (class "Default")
      (node (ref "D16") (pin "2") (pinfunction "A_2") (pintype "passive"))
      (node (ref "SW16") (pin "1") (pinfunction "1_1") (pintype "passive"))
    )
    (net (code "29") (name "Net-(D17-A)") (class "Default")
      (node (ref "D17") (pin "2") (pinfunction "A_2") (pintype "passive"))
      (node (ref "SW17") (pin "1") (pinfunction "1_1") (pintype "passive"))
    )
    (net (code "30") (name "Net-(D18-A)") (class "Default")
      (node (ref "D18") (pin "2") (pinfunction "A_2") (pintype "passive"))
      (node (ref "SW18") (pin "1") (pinfunction "1_1") (pintype "passive"))
    )
    (net (code "31") (name "Net-(D19-A)") (class "Default")
      (node (ref "D19") (pin "2") (pinfunction "A_2") (pintype "passive"))
      (node (ref "SW19") (pin "1") (pinfunction "1_1") (pintype "passive"))
    )
    (net (code "32") (name "Net-(D20-A)") (class "Default")
      (node (ref "D20") (pin "2") (pinfunction "A_2") (pintype "passive"))
      (node (ref "SW20") (pin "1") (pinfunction "1_1") (pintype "passive"))
    )
    (net (code "33") (name "Net-(D21-A)") (class "Default")
      (node (ref "D21") (pin "2") (pinfunction "A_2") (pintype "passive"))
      (node (ref "SW21") (pin "1") (pinfunction "1_1") (pintype "passive"))
    )
    (net (code "34") (name "Net-(D22-A)") (class "Default")
      (node (ref "D22") (pin "2") (pinfunction "A_2") (pintype "passive"))
      (node (ref "SW22") (pin "1") (pinfunction "1_1") (pintype "passive"))
    )
    (net (code "35") (name "Net-(D23-A)") (class "Default")
      (node (ref "D23") (pin "2") (pinfunction "A_2") (pintype "passive"))
      (node (ref "SW23") (pin "1") (pinfunction "1_1") (pintype "passive"))
    )
    (net (code "36") (name "Net-(D24-A)") (class "Default")
      (node (ref "D24") (pin "2") (pinfunction "A_2") (pintype "passive"))
      (node (ref "SW24") (pin "1") (pinfunction "1_1") (pintype "passive"))
    )
    (net (code "37") (name "Net-(D25-A)") (class "Default")
      (node (ref "D25") (pin "2") (pinfunction "A_2") (pintype "passive"))
      (node (ref "SW25") (pin "1") (pinfunction "1_1") (pintype "passive"))
    )
    (net (code "38") (name "Net-(D26-A)") (class "Default")
      (node (ref "D26") (pin "2") (pinfunction "A_2") (pintype "passive"))
      (node (ref "SW26") (pin "1") (pinfunction "1_1") (pintype "passive"))
    )
    (net (code "39") (name "Net-(D27-A)") (class "Default")
      (node (ref "D27") (pin "2") (pinfunction "A_2") (pintype "passive"))
      (node (ref "SW27") (pin "1") (pinfunction "1_1") (pintype "passive"))
    )
    (net (code "40") (name "Net-(D28-A)") (class "Default")
      (node (ref "D28") (pin "2") (pinfunction "A_2") (pintype "passive"))
      (node (ref "SW28") (pin "1") (pinfunction "1_1") (pintype "passive"))
    )
    (net (code "41") (name "Net-(D29-A)") (class "Default")
      (node (ref "D29") (pin "2") (pinfunction "A_2") (pintype "passive"))
      (node (ref "SW29") (pin "1") (pinfunction "1_1") (pintype "passive"))
    )
    (net (code "42") (name "Net-(D30-A)") (class "Default")
      (node (ref "D30") (pin "2") (pinfunction "A_2") (pintype "passive"))
      (node (ref "SW30") (pin "1") (pinfunction "1_1") (pintype "passive"))
    )
    (net (code "43") (name "Net-(D31-A)") (class "Default")
      (node (ref "D31") (pin "2") (pinfunction "A_2") (pintype "passive"))
      (node (ref "SW31") (pin "1") (pinfunction "1_1") (pintype "passive"))
    )
    (net (code "44") (name "Net-(D32-A)") (class "Default")
      (node (ref "D32") (pin "2") (pinfunction "A_2") (pintype "passive"))
      (node (ref "SW32") (pin "1") (pinfunction "1_1") (pintype "passive"))
    )
    (net (code "45") (name "Net-(D33-A)") (class "Default")
      (node (ref "D33") (pin "2") (pinfunction "A_2") (pintype "passive"))
      (node (ref "SW33") (pin "1") (pinfunction "1_1") (pintype "passive"))
    )
    (net (code "46") (name "Net-(D34-A)") (class "Default")
      (node (ref "D34") (pin "2") (pinfunction "A_2") (pintype "passive"))
      (node (ref "SW34") (pin "1") (pinfunction "1_1") (pintype "passive"))
    )
    (net (code "47") (name "Net-(D35-A)") (class "Default")
      (node (ref "D35") (pin "2") (pinfunction "A_2") (pintype "passive"))
      (node (ref "SW35") (pin "1") (pinfunction "1_1") (pintype "passive"))
    )
    (net (code "48") (name "Net-(D36-A)") (class "Default")
      (node (ref "D36") (pin "2") (pinfunction "A_2") (pintype "passive"))
      (node (ref "SW36") (pin "1") (pinfunction "1_1") (pintype "passive"))
    )
    (net (code "49") (name "Net-(D37-A)") (class "Default")
      (node (ref "D37") (pin "2") (pinfunction "A_2") (pintype "passive"))
      (node (ref "SW37") (pin "1") (pinfunction "1_1") (pintype "passive"))
    )
    (net (code "50") (name "Net-(D38-A)") (class "Default")
      (node (ref "D38") (pin "2") (pinfunction "A_2") (pintype "passive"))
      (node (ref "SW38") (pin "1") (pinfunction "1_1") (pintype "passive"))
    )
    (net (code "51") (name "Net-(D39-A)") (class "Default")
      (node (ref "D39") (pin "2") (pinfunction "A_2") (pintype "passive"))
      (node (ref "SW39") (pin "1") (pinfunction "1_1") (pintype "passive"))
    )
    (net (code "52") (name "Net-(D40-A)") (class "Default")
      (node (ref "D40") (pin "2") (pinfunction "A_2") (pintype "passive"))
      (node (ref "SW40") (pin "1") (pinfunction "1_1") (pintype "passive"))
    )
    (net (code "53") (name "Net-(D41-A)") (class "Default")
      (node (ref "D41") (pin "2") (pinfunction "A_2") (pintype "passive"))
      (node (ref "SW41") (pin "1") (pinfunction "1_1") (pintype "passive"))
    )
    (net (code "54") (name "Net-(D42-A)") (class "Default")
      (node (ref "D42") (pin "2") (pinfunction "A_2") (pintype "passive"))
      (node (ref "SW42") (pin "1") (pinfunction "1_1") (pintype "passive"))
    )
    (net (code "55") (name "Net-(D43-A)") (class "Default")
      (node (ref "D43") (pin "2") (pinfunction "A_2") (pintype "passive"))
      (node (ref "SW43") (pin "1") (pinfunction "1_1") (pintype "passive"))
    )
    (net (code "56") (name "Net-(D44-A)") (class "Default")
      (node (ref "D44") (pin "2") (pinfunction "A_2") (pintype "passive"))
      (node (ref "SW44") (pin "1") (pinfunction "1_1") (pintype "passive"))
    )
    (net (code "57") (name "Net-(D45-A)") (class "Default")
      (node (ref "D45") (pin "2") (pinfunction "A_2") (pintype "passive"))
      (node (ref "SW45") (pin "1") (pinfunction "1_1") (pintype "passive"))
    )
    (net (code "58") (name "Net-(D46-A)") (class "Default")
      (node (ref "D46") (pin "2") (pinfunction "A_2") (pintype "passive"))
      (node (ref "SW46") (pin "1") (pinfunction "1_1") (pintype "passive"))
    )
    (net (code "59") (name "Net-(D47-A)") (class "Default")
      (node (ref "D47") (pin "2") (pinfunction "A_2") (pintype "passive"))
      (node (ref "SW47") (pin "1") (pinfunction "1_1") (pintype "passive"))
    )
    (net (code "60") (name "Net-(D48-A)") (class "Default")
      (node (ref "D48") (pin "2") (pinfunction "A_2") (pintype "passive"))
      (node (ref "SW48") (pin "1") (pinfunction "1_1") (pintype "passive"))
    )
  )
)
